# Motor.net
KiCad netlist of a schematic drawn in Altium Designer
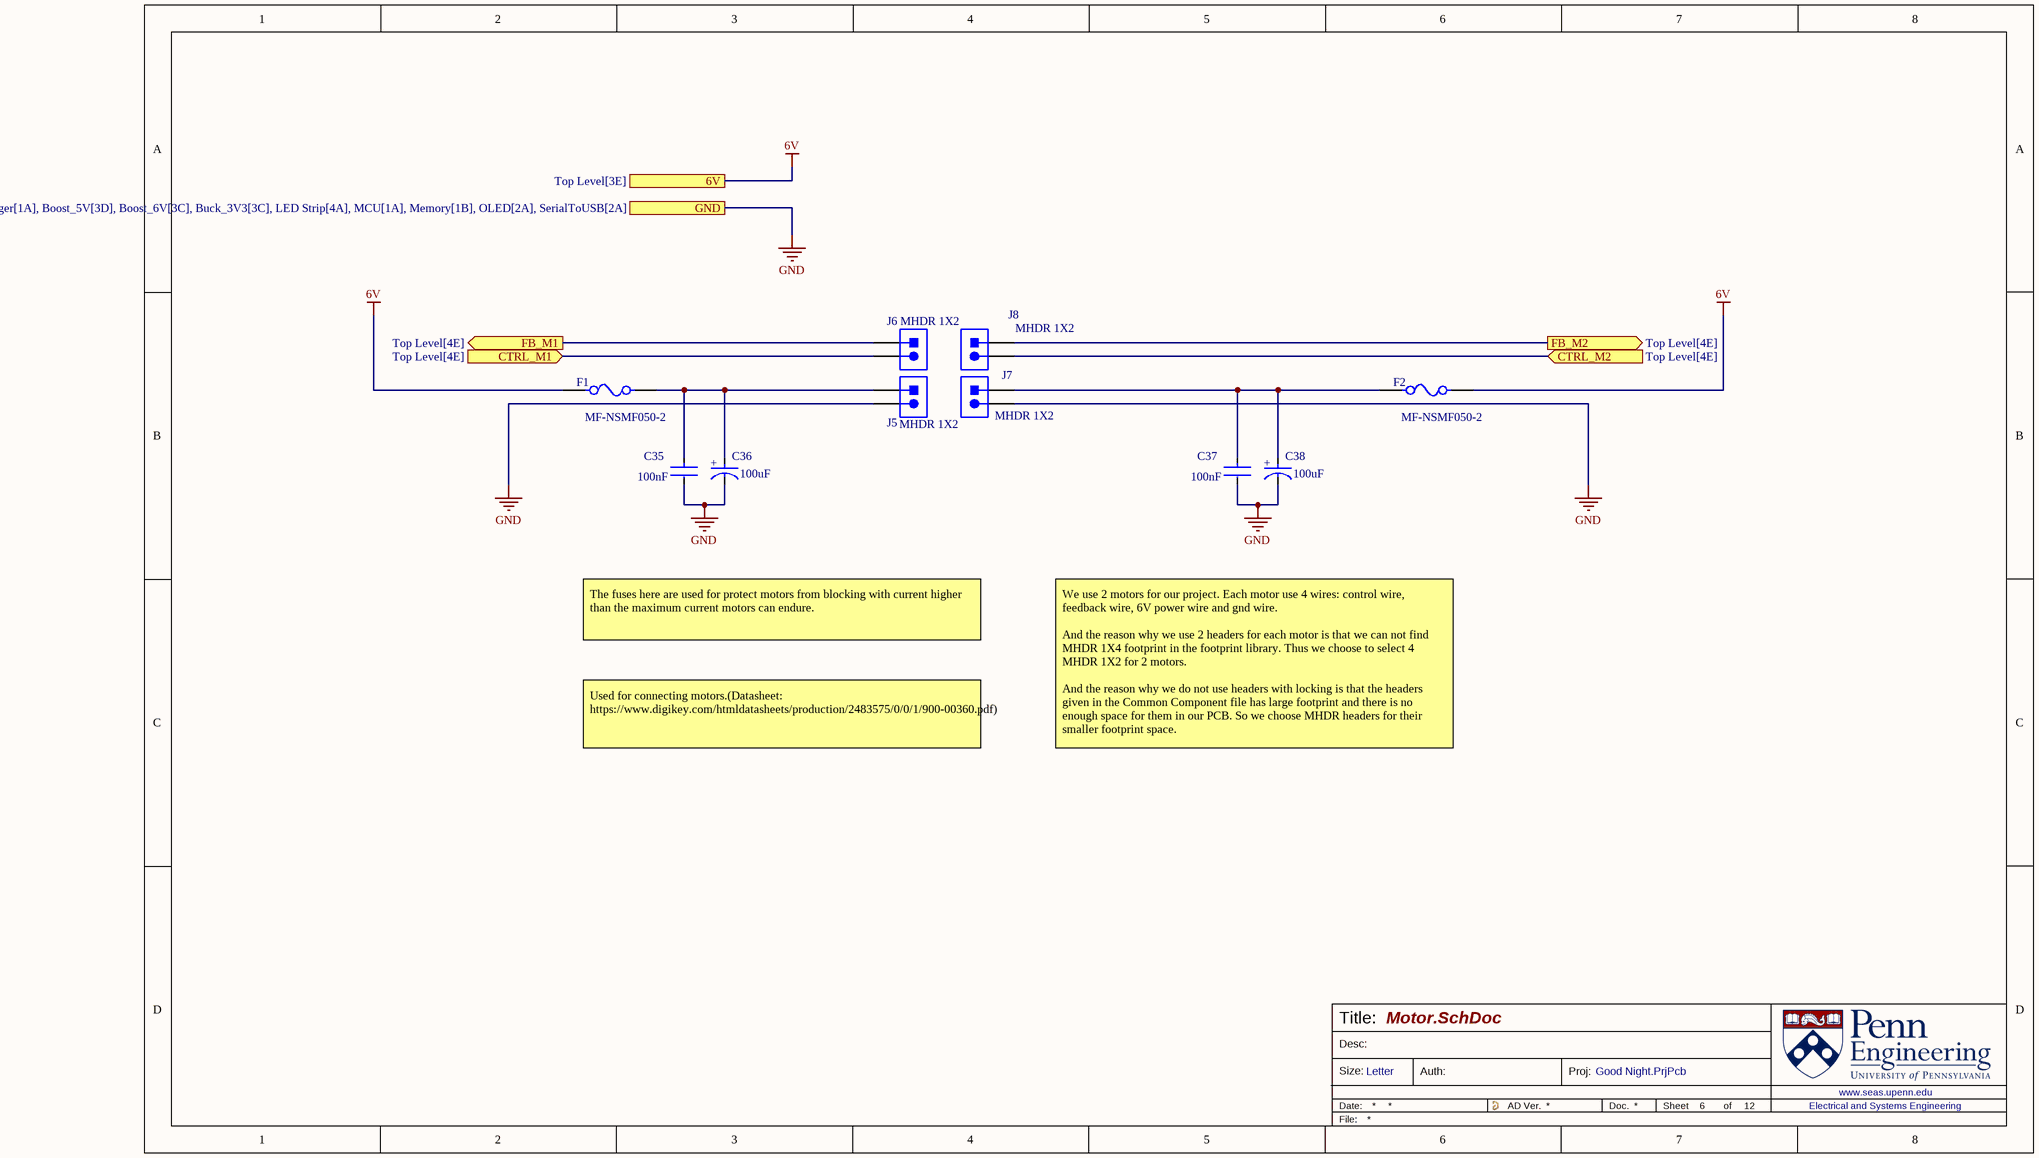
[diagram p0: Motor.SchDoc]

(export (version "E")
  (design (tool "Eeschema 10.0.6"))
  (components
    (comp (ref "C35")
      (value "100nF")
      (footprint "FP-CC0603-DA-MFG")
      (description "CAP CER 0.1UF 16V X7R 0603")
      (fields
        (field (name "OCTOPART") "https://octopart.com/cc0603krx7r7bb104-yageo-192941")
        (field (name "TOLERANCE") "0.1")
      )
      (libsource (lib "Altium Content Vault") (part "11868f565c42a9108669ba33697ecf6"))
    )
    (comp (ref "C36")
      (value "100uF")
      (footprint "FP-RAD-TH-D_8_0_5-L_11_5-MFG")
      (description "Aluminum Electrolytic Capacitors (Radial Lead Type) 100uF ±20% 50V")
      (fields (field (name "VOLTAGE") "50V") (field (name "TOLERANCE") "20%"))
      (libsource (lib "Altium Content Vault") (part "a00bbbee19879c290e62620ae7e47b1"))
    )
    (comp (ref "C37")
      (value "100nF")
      (footprint "FP-CC0603-DA-MFG")
      (description "CAP CER 0.1UF 16V X7R 0603")
      (fields
        (field (name "OCTOPART") "https://octopart.com/cc0603krx7r7bb104-yageo-192941")
        (field (name "TOLERANCE") "0.1")
      )
      (libsource (lib "Altium Content Vault") (part "11868f565c42a9108669ba33697ecf6"))
    )
    (comp (ref "C38")
      (value "100uF")
      (footprint "FP-RAD-TH-D_8_0_5-L_11_5-MFG")
      (description "Aluminum Electrolytic Capacitors (Radial Lead Type) 100uF ±20% 50V")
      (fields (field (name "VOLTAGE") "50V") (field (name "TOLERANCE") "20%"))
      (libsource (lib "Altium Content Vault") (part "a00bbbee19879c290e62620ae7e47b1"))
    )
    (comp (ref "F1")
      (value "MF-NSMF050-2")
      (footprint "FP-MF-NSMF050-2-MFG")
      (description "PTC RESET FUSE 13.2V 500MA 1206")
      (fields
        (field (name "MANUFACTURER") "Bourns")
        (field (name "OCTOPART") "https://octopart.com/mf-nsmf050-2-bourns-34532")
      )
      (libsource (lib "Altium Content Vault") (part "5bcf9b9f640e542cf0359d10258e979"))
    )
    (comp (ref "F2")
      (value "MF-NSMF050-2")
      (footprint "FP-MF-NSMF050-2-MFG")
      (description "PTC RESET FUSE 13.2V 500MA 1206")
      (fields
        (field (name "MANUFACTURER") "Bourns")
        (field (name "OCTOPART") "https://octopart.com/mf-nsmf050-2-bourns-34532")
      )
      (libsource (lib "Altium Content Vault") (part "5bcf9b9f640e542cf0359d10258e979"))
    )
    (comp (ref "J5")
      (value "MHDR 1X2")
      (footprint "PH1-02-UA")
      (description "Header, 2-Pin, 0.1in Pitch, Male")
      (libsource (lib "University of Pennsylvania (ESE)") (part "Header 1X2"))
    )
    (comp (ref "J6")
      (value "MHDR 1X2")
      (footprint "PH1-02-UA")
      (description "Header, 2-Pin, 0.1in Pitch, Male")
      (libsource (lib "University of Pennsylvania (ESE)") (part "Header 1X2"))
    )
    (comp (ref "J7")
      (value "MHDR 1X2")
      (footprint "PH1-02-UA")
      (description "Header, 2-Pin, 0.1in Pitch, Male")
      (libsource (lib "") (part "Header 1X2_1"))
    )
    (comp (ref "J8")
      (value "MHDR 1X2")
      (footprint "PH1-02-UA")
      (description "Header, 2-Pin, 0.1in Pitch, Male")
      (libsource (lib "") (part "Header 1X2_1"))
    )
  )
  (nets
    (net (code "1") (name "/CTRL_M1") (class "Default")
      (node (ref "J6") (pin "2") (pinfunction "2_2") (pintype "passive"))
    )
    (net (code "2") (name "/CTRL_M2") (class "Default")
      (node (ref "J8") (pin "2") (pinfunction "2_2") (pintype "passive"))
    )
    (net (code "3") (name "/FB_M1") (class "Default")
      (node (ref "J6") (pin "1") (pinfunction "1_1") (pintype "passive"))
    )
    (net (code "4") (name "/FB_M2") (class "Default")
      (node (ref "J8") (pin "1") (pinfunction "1_1") (pintype "passive"))
    )
    (net (code "5") (name "6V") (class "Default")
      (node (ref "F1") (pin "1") (pinfunction "1_1") (pintype "passive"))
      (node (ref "F2") (pin "2") (pinfunction "2_2") (pintype "passive"))
    )
    (net (code "6") (name "GND") (class "Default")
      (node (ref "C35") (pin "2") (pinfunction "2_2") (pintype "passive"))
      (node (ref "C36") (pin "1") (pinfunction "C_1") (pintype "passive"))
      (node (ref "C37") (pin "2") (pinfunction "2_2") (pintype "passive"))
      (node (ref "C38") (pin "1") (pinfunction "C_1") (pintype "passive"))
      (node (ref "J5") (pin "2") (pinfunction "2_2") (pintype "passive"))
      (node (ref "J7") (pin "2") (pinfunction "2_2") (pintype "passive"))
    )
    (net (code "7") (name "Net-(C36-A)") (class "Default")
      (node (ref "C35") (pin "1") (pinfunction "1_1") (pintype "passive"))
      (node (ref "C36") (pin "2") (pinfunction "A_2") (pintype "passive"))
      (node (ref "F1") (pin "2") (pinfunction "2_2") (pintype "passive"))
      (node (ref "J5") (pin "1") (pinfunction "1_1") (pintype "passive"))
    )
    (net (code "8") (name "Net-(C38-A)") (class "Default")
      (node (ref "C37") (pin "1") (pinfunction "1_1") (pintype "passive"))
      (node (ref "C38") (pin "2") (pinfunction "A_2") (pintype "passive"))
      (node (ref "F2") (pin "1") (pinfunction "1_1") (pintype "passive"))
      (node (ref "J7") (pin "1") (pinfunction "1_1") (pintype "passive"))
    )
  )
)
